# USB.net
KiCad netlist of a schematic drawn in Altium Designer
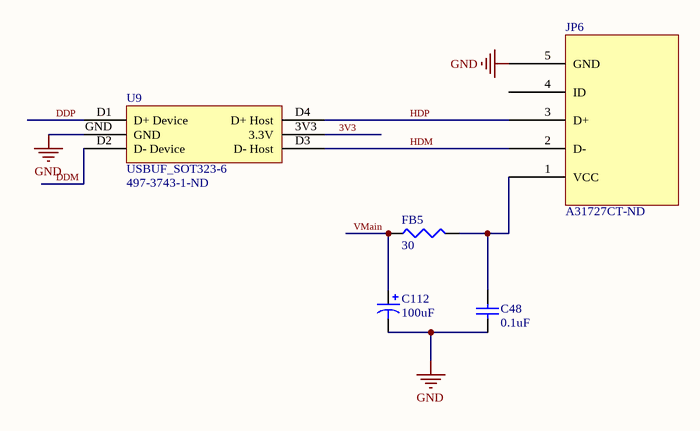
[diagram p0: USB.SchDoc]

(export (version "E")
  (design (tool "Eeschema 10.0.6"))
  (components
    (comp (ref "C48")
      (value "0.1uF")
      (footprint "CAPC2008X06N")
      (description "CAP CER 0.1UF 50V 10% X7R 0805")
      (fields (field (name "Comment") "Kemet_0805_a_0.1uF"))
      (libsource (lib "Capacitors") (part "Kemet_0805_a_0.1uF"))
    )
    (comp (ref "C112")
      (value "100uF")
      (footprint "6032")
      (description "CAP TANT 100UF 10V 10% LOESR SMD")
      (fields (field (name "Comment") "TantCap_6032_100uF"))
      (libsource (lib "my_KEMET") (part "TantCap_6032_100uF"))
    )
    (comp (ref "FB5")
      (value "Murata_a_0805_30_Ohm_100Mhz")
      (footprint "0805")
      (description "FERRITE CHIP 30 OHM 3000MA 0805")
      (fields (field (name "VALUE @ 100MHZ") "30"))
      (libsource (lib "Filters") (part "Murata_a_0805_30_Ohm_100Mhz"))
    )
    (comp (ref "JP6")
      (value "Mini USB B")
      (footprint "PCBComponent_1")
      (description "Mini B USB Receptacle Type B")
      (fields (field (name "SUPPLIER PART NUMBER 1") "A31727CT-ND"))
      (libsource (lib "TE Connectivity") (part "Mini USB B"))
    )
    (comp (ref "U9")
      (value "USBUF_SOT323-6")
      (footprint "SOT65P210X110-6N")
      (description "EMI FIlter and Line Termination for USB Upstream Ports")
      (fields
        (field (name "MANUFACTURER") "ST Microelectronics")
        (field (name "SUPPLIER PART NUMBER 1") "497-3743-1-ND")
      )
      (libsource (lib "ST Microelectronics") (part "USBUF_SOT323-6"))
    )
  )
  (nets
    (net (code "1") (name "/3V3") (class "Default")
      (node (ref "U9") (pin "3V3") (pinfunction "3.3V_3V3") (pintype "passive"))
    )
    (net (code "2") (name "/DDM") (class "Default")
      (node (ref "U9") (pin "D2") (pinfunction "D-_Device_D2") (pintype "passive"))
    )
    (net (code "3") (name "/DDP") (class "Default")
      (node (ref "U9") (pin "D1") (pinfunction "D+_Device_D1") (pintype "passive"))
    )
    (net (code "4") (name "/HDM") (class "Default")
      (node (ref "JP6") (pin "2") (pinfunction "D-_2") (pintype "passive"))
      (node (ref "U9") (pin "D3") (pinfunction "D-_Host_D3") (pintype "passive"))
    )
    (net (code "5") (name "/HDP") (class "Default")
      (node (ref "JP6") (pin "3") (pinfunction "D+_3") (pintype "passive"))
      (node (ref "U9") (pin "D4") (pinfunction "D+_Host_D4") (pintype "passive"))
    )
    (net (code "6") (name "/VMain") (class "Default")
      (node (ref "C112") (pin "1") (pinfunction "1_1") (pintype "passive"))
      (node (ref "FB5") (pin "1") (pinfunction "1_1") (pintype "passive"))
    )
    (net (code "7") (name "GND") (class "Default")
      (node (ref "C112") (pin "2") (pinfunction "2_2") (pintype "passive"))
      (node (ref "C48") (pin "1") (pinfunction "1_1") (pintype "passive"))
      (node (ref "JP6") (pin "5") (pinfunction "GND_5") (pintype "power_in"))
      (node (ref "U9") (pin "GND") (pinfunction "GND_GND") (pintype "passive"))
    )
    (net (code "8") (name "Net-(JP6-VCC)") (class "Default")
      (node (ref "C48") (pin "2") (pinfunction "2_2") (pintype "passive"))
      (node (ref "FB5") (pin "2") (pinfunction "2_2") (pintype "passive"))
      (node (ref "JP6") (pin "1") (pinfunction "VCC_1") (pintype "power_in"))
    )
    (net (code "9") (name "unconnected-(JP6-ID-Pad4)") (class "Default")
      (node (ref "JP6") (pin "4") (pinfunction "ID_4") (pintype "passive"))
    )
  )
)
